# 5kHz_GEN_LPF.net
KiCad netlist of a schematic drawn in Altium Designer
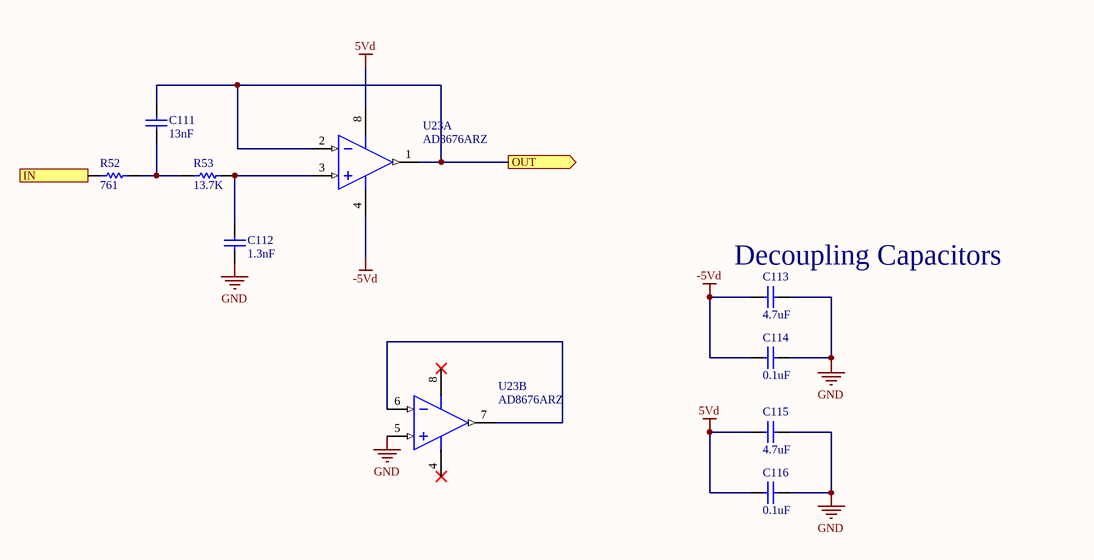
[diagram p0: 5kHz_GEN_LPF.SchDoc]

(export (version "E")
  (design (tool "Eeschema 10.0.6"))
  (components
    (comp (ref "C111")
      (value "13nF")
      (footprint "0402_Cap")
      (description "Capacitor, 16nF, 0805, 25V")
      (libsource (lib "Arturo_Approved") (part "08051C163JAT2A"))
    )
    (comp (ref "C112")
      (value "1.3nF")
      (footprint "0402_Cap")
      (description "Capacitor, 1.6nF, 0805, 25V")
      (libsource (lib "Arturo_Approved") (part "GRM2165C2A162JA01D"))
    )
    (comp (ref "C113")
      (value "4.7uF")
      (footprint "0402_Cap")
      (description "Capacitor, 4.7uF, 0805")
      (libsource (lib "Arturo_Approved") (part "CL21A475KAQNNNE"))
    )
    (comp (ref "C114")
      (value "0.1uF")
      (footprint "0402_Cap")
      (description "Capacitor, 0.1uF, 0805")
      (libsource (lib "Arturo_Approved") (part "CL21B104KACNNNC"))
    )
    (comp (ref "C115")
      (value "4.7uF")
      (footprint "0402_Cap")
      (description "Capacitor, 4.7uF, 0805")
      (libsource (lib "Arturo_Approved") (part "CL21A475KAQNNNE"))
    )
    (comp (ref "C116")
      (value "0.1uF")
      (footprint "0402_Cap")
      (description "Capacitor, 0.1uF, 0805")
      (libsource (lib "Arturo_Approved") (part "CL21B104KACNNNC"))
    )
    (comp (ref "R52")
      (value "761")
      (footprint "0402_Res")
      (description "1.65k")
      (libsource (lib "Arturo_Approved") (part "RC0805FR-071K65L"))
    )
    (comp (ref "R53")
      (value "13.7K")
      (footprint "0402_Res")
      (description "5.9k")
      (libsource (lib "Arturo_Approved") (part "RC0805FR-075K9L"))
    )
    (comp (ref "U23")
      (value "AD8676ARZ")
      (footprint "ADI-R-8_M")
      (fields (field (name "GENERIC PART NUMBER") "AD8676") (field (name "MANUFACTURER") "Analog Devices"))
      (libsource (lib "Altium Content Vault") (part "ADI-OP29X-R-8"))
    )
  )
  (nets
    (net (code "1") (name "-5Vd") (class "Default")
      (node (ref "C113") (pin "1") (pinfunction "1_1") (pintype "passive"))
      (node (ref "C114") (pin "1") (pinfunction "1_1") (pintype "passive"))
      (node (ref "U23") (pin "4") (pinfunction "-V_4") (pintype "power_in"))
    )
    (net (code "2") (name "/IN") (class "Default")
      (node (ref "R52") (pin "1") (pinfunction "1_1") (pintype "passive"))
    )
    (net (code "3") (name "/OUT") (class "Default")
      (node (ref "C111") (pin "2") (pinfunction "2_2") (pintype "passive"))
      (node (ref "U23") (pin "1") (pinfunction "OUT_A_1") (pintype "output"))
      (node (ref "U23") (pin "2") (pinfunction "-IN_A_2") (pintype "input"))
    )
    (net (code "4") (name "5Vd") (class "Default")
      (node (ref "C115") (pin "1") (pinfunction "1_1") (pintype "passive"))
      (node (ref "C116") (pin "1") (pinfunction "1_1") (pintype "passive"))
      (node (ref "U23") (pin "8") (pinfunction "+V_8") (pintype "power_in"))
    )
    (net (code "5") (name "GND") (class "Default")
      (node (ref "C112") (pin "1") (pinfunction "1_1") (pintype "passive"))
      (node (ref "C113") (pin "2") (pinfunction "2_2") (pintype "passive"))
      (node (ref "C114") (pin "2") (pinfunction "2_2") (pintype "passive"))
      (node (ref "C115") (pin "2") (pinfunction "2_2") (pintype "passive"))
      (node (ref "C116") (pin "2") (pinfunction "2_2") (pintype "passive"))
      (node (ref "U23") (pin "5") (pinfunction "+IN_B_5") (pintype "input"))
    )
    (net (code "6") (name "Net-(C111-Pad1)") (class "Default")
      (node (ref "C111") (pin "1") (pinfunction "1_1") (pintype "passive"))
      (node (ref "R52") (pin "2") (pinfunction "2_2") (pintype "passive"))
      (node (ref "R53") (pin "1") (pinfunction "1_1") (pintype "passive"))
    )
    (net (code "7") (name "Net-(U23A-+IN_A)") (class "Default")
      (node (ref "C112") (pin "2") (pinfunction "2_2") (pintype "passive"))
      (node (ref "R53") (pin "2") (pinfunction "2_2") (pintype "passive"))
      (node (ref "U23") (pin "3") (pinfunction "+IN_A_3") (pintype "input"))
    )
    (net (code "8") (name "Net-(U23B--IN_B)") (class "Default")
      (node (ref "U23") (pin "6") (pinfunction "-IN_B_6") (pintype "input"))
      (node (ref "U23") (pin "7") (pinfunction "OUT_B_7") (pintype "output"))
    )
    (net (code "9") (name "unconnected-(U23B-+V-Pad8)") (class "Default")
      (node (ref "U23") (pin "8") (pinfunction "+V_8") (pintype "power_in+no_connect"))
    )
    (net (code "10") (name "unconnected-(U23B--V-Pad4)") (class "Default")
      (node (ref "U23") (pin "4") (pinfunction "-V_4") (pintype "power_in+no_connect"))
    )
  )
)
